# STM32F411CEU6.net
KiCad netlist of a schematic drawn in Altium Designer
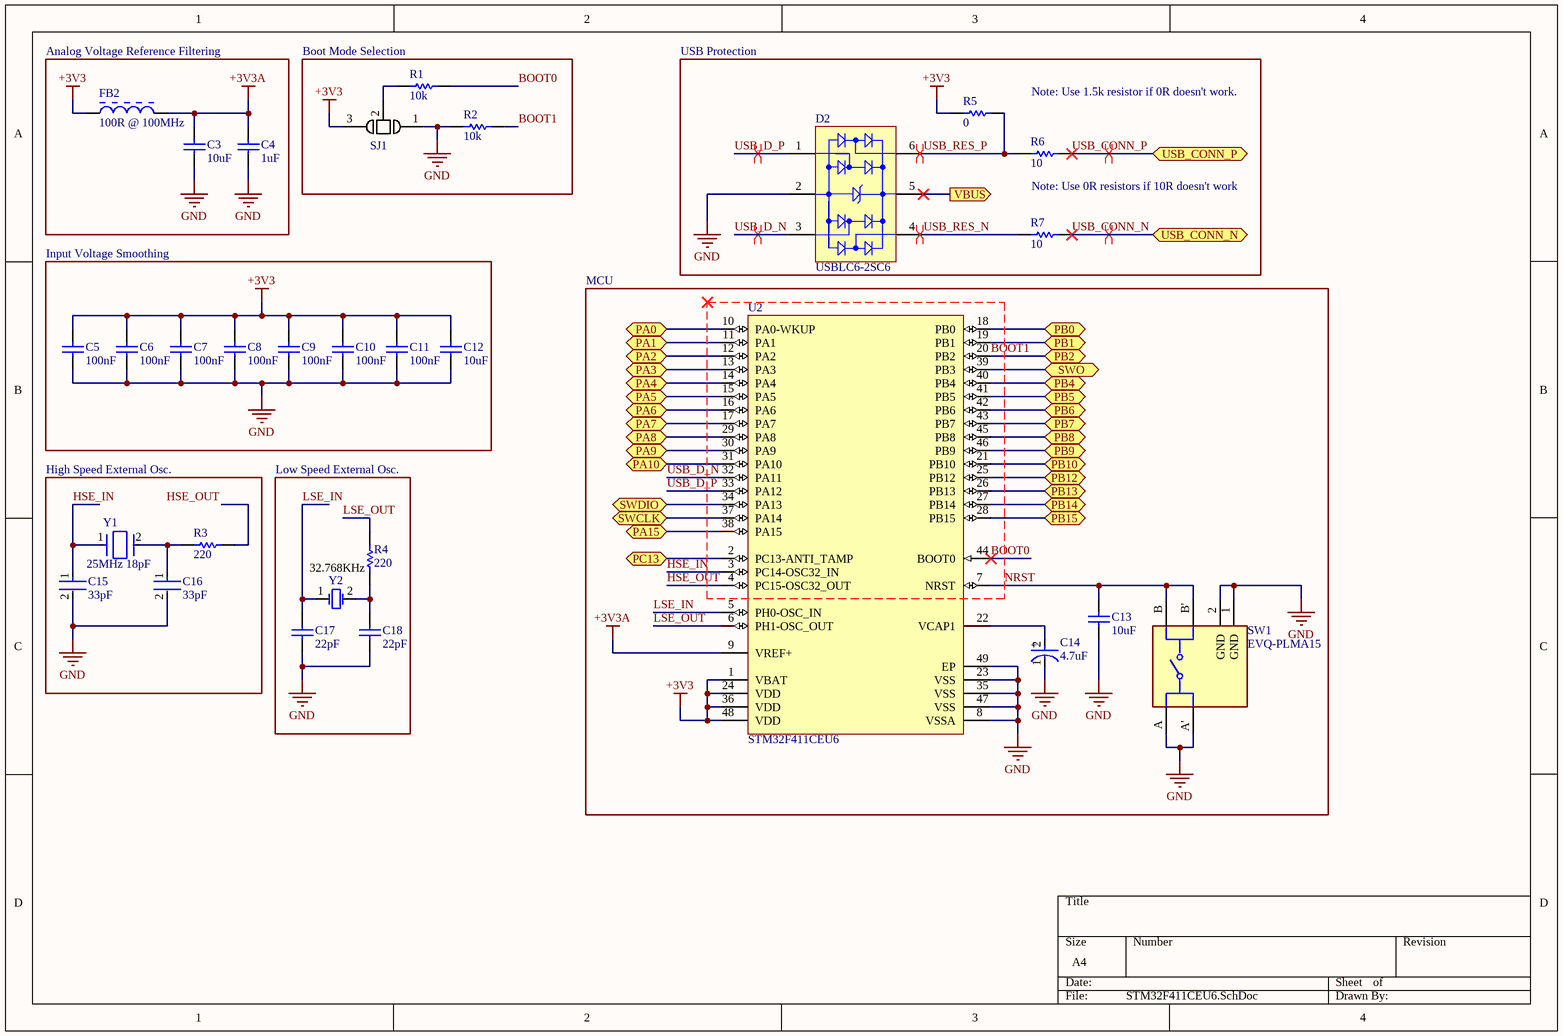
[diagram p0: STM32F411CEU6.SchDoc]

(export (version "E")
  (design (tool "Eeschema 10.0.6"))
  (components
    (comp (ref "C3")
      (value "10uF")
      (footprint "CAPC3216X180X50LL20T30")
      (description "Chip Capacitor, 10 uF, +/- 10%, 25 V, -55 to 85 degC, 1206 (3216 Metric), RoHS, Tape and Reel")
      (fields
        (field (name "MANUFACTURER") "Samsung Electro-Mechanics")
        (field (name "MANUFACTURER PART NUMBER") "CL31A106KAHNNNE")
      )
      (libsource (lib "Altium Content Vault") (part "CAP-NP-2"))
    )
    (comp (ref "C4")
      (value "1uF")
      (footprint "CAPC2013X140X50NL20T25")
      (fields
        (field (name "PART NUMBER") "C0805C105J4RACTU")
        (field (name "MANUFACTURER") "Kemet")
        (field (name "TOLERANCE") "5%")
      )
      (libsource (lib "Altium Content Vault") (part "CAP"))
    )
    (comp (ref "C5")
      (value "100nF")
      (footprint "CAPC2013X94X50LL20T25")
      (description "Chip Capacitor, 0.1 uF, +/- 5%, 50 V, -55 to 125 degC, 0805 (2012 Metric), RoHS, Tape and Reel")
      (fields (field (name "TOLERANCE") "5%") (field (name "MANUFACTURER") "AVX"))
      (libsource (lib "Altium Content Vault") (part "CAP-NP-2"))
    )
    (comp (ref "C6")
      (value "100nF")
      (footprint "CAPC2013X94X50LL20T25")
      (description "Chip Capacitor, 0.1 uF, +/- 5%, 50 V, -55 to 125 degC, 0805 (2012 Metric), RoHS, Tape and Reel")
      (fields (field (name "TOLERANCE") "5%") (field (name "MANUFACTURER") "AVX"))
      (libsource (lib "Altium Content Vault") (part "CAP-NP-2"))
    )
    (comp (ref "C7")
      (value "100nF")
      (footprint "CAPC2013X94X50LL20T25")
      (description "Chip Capacitor, 0.1 uF, +/- 5%, 50 V, -55 to 125 degC, 0805 (2012 Metric), RoHS, Tape and Reel")
      (fields (field (name "TOLERANCE") "5%") (field (name "MANUFACTURER") "AVX"))
      (libsource (lib "Altium Content Vault") (part "CAP-NP-2"))
    )
    (comp (ref "C8")
      (value "100nF")
      (footprint "CAPC2013X94X50LL20T25")
      (description "Chip Capacitor, 0.1 uF, +/- 5%, 50 V, -55 to 125 degC, 0805 (2012 Metric), RoHS, Tape and Reel")
      (fields (field (name "TOLERANCE") "5%") (field (name "MANUFACTURER") "AVX"))
      (libsource (lib "Altium Content Vault") (part "CAP-NP-2"))
    )
    (comp (ref "C9")
      (value "100nF")
      (footprint "CAPC2013X94X50LL20T25")
      (description "Chip Capacitor, 0.1 uF, +/- 5%, 50 V, -55 to 125 degC, 0805 (2012 Metric), RoHS, Tape and Reel")
      (fields (field (name "TOLERANCE") "5%") (field (name "MANUFACTURER") "AVX"))
      (libsource (lib "Altium Content Vault") (part "CAP-NP-2"))
    )
    (comp (ref "C10")
      (value "100nF")
      (footprint "CAPC2013X94X50LL20T25")
      (description "Chip Capacitor, 0.1 uF, +/- 5%, 50 V, -55 to 125 degC, 0805 (2012 Metric), RoHS, Tape and Reel")
      (fields (field (name "TOLERANCE") "5%") (field (name "MANUFACTURER") "AVX"))
      (libsource (lib "Altium Content Vault") (part "CAP-NP-2"))
    )
    (comp (ref "C11")
      (value "100nF")
      (footprint "CAPC2013X94X50LL20T25")
      (description "Chip Capacitor, 0.1 uF, +/- 5%, 50 V, -55 to 125 degC, 0805 (2012 Metric), RoHS, Tape and Reel")
      (fields (field (name "TOLERANCE") "5%") (field (name "MANUFACTURER") "AVX"))
      (libsource (lib "Altium Content Vault") (part "CAP-NP-2"))
    )
    (comp (ref "C12")
      (value "10uF")
      (footprint "CAPC3216X180X50LL20T30")
      (description "Chip Capacitor, 10 uF, +/- 10%, 25 V, -55 to 85 degC, 1206 (3216 Metric), RoHS, Tape and Reel")
      (fields
        (field (name "MANUFACTURER") "Samsung Electro-Mechanics")
        (field (name "MANUFACTURER PART NUMBER") "CL31A106KAHNNNE")
      )
      (libsource (lib "Altium Content Vault") (part "CAP-NP-2"))
    )
    (comp (ref "C13")
      (value "10uF")
      (footprint "CAPC3216X180X50LL20T30")
      (description "Chip Capacitor, 10 uF, +/- 10%, 25 V, -55 to 85 degC, 1206 (3216 Metric), RoHS, Tape and Reel")
      (fields
        (field (name "MANUFACTURER") "Samsung Electro-Mechanics")
        (field (name "MANUFACTURER PART NUMBER") "CL31A106KAHNNNE")
      )
      (libsource (lib "Altium Content Vault") (part "CAP-NP-2"))
    )
    (comp (ref "C14")
      (value "4.7uF")
      (footprint "FP-F38M-MFG")
      (description "CAP TANT POLY 4.7UF 10V SMD")
      (fields
        (field (name "TOLERANCE") "20%")
        (field (name "OCTOPART") "https://octopart.com/f381a475mma-avx-30375031")
      )
      (libsource (lib "Altium Content Vault") (part "cf48714ba7e38822c1575c7ec0b6d1f"))
    )
    (comp (ref "C15")
      (value "33pF")
      (footprint "FP-CL790-IPC_C")
      (description "Cap Ceramic 33pF 50V C0G ±5% SMD 0402 +125°C Paper T/R")
      (fields (field (name "TOLERANCE") "5%") (field (name "VOLTAGE") "50V"))
      (libsource (lib "Altium Content Vault") (part "b4654b650e69147ec39a6b967a45e02"))
    )
    (comp (ref "C16")
      (value "33pF")
      (footprint "FP-CL790-IPC_C")
      (description "Cap Ceramic 33pF 50V C0G ±5% SMD 0402 +125°C Paper T/R")
      (fields (field (name "TOLERANCE") "5%") (field (name "VOLTAGE") "50V"))
      (libsource (lib "Altium Content Vault") (part "b4654b650e69147ec39a6b967a45e02"))
    )
    (comp (ref "C17")
      (value "22pF")
      (footprint "CAPC2012X88X50ML20T25")
      (fields
        (field (name "MANUFACTURER") "Kemet")
        (field (name "PART NUMBER") "C0805C220J5GACTU")
        (field (name "TOLERANCE") "5%")
      )
      (libsource (lib "Altium Content Vault") (part "CAP"))
    )
    (comp (ref "C18")
      (value "22pF")
      (footprint "CAPC2012X88X50ML20T25")
      (fields
        (field (name "MANUFACTURER") "Kemet")
        (field (name "PART NUMBER") "C0805C220J5GACTU")
        (field (name "TOLERANCE") "5%")
      )
      (libsource (lib "Altium Content Vault") (part "CAP"))
    )
    (comp (ref "D2")
      (value "USBLC6-2SC6")
      (footprint "STM-SOT23-6L_V")
      (description "Very low capacitance ESD protection, 3.5 pF, -40 to 125 degC, 6-Pin SOT23, RoHS, Tape and Reel")
      (fields (field (name "MANUFACTURER") "STMicroelectronics"))
      (libsource (lib "Altium Content Vault") (part "STM-USB_DVI_HDMIULC6-4SC6X-SOT23-6L"))
    )
    (comp (ref "FB2")
      (value "100R @ 100MHz")
      (footprint "MURA-BLM18PG_KG-B25-CHIP-2_V1")
      (description "MURATA - BLM18PG121SN1D - FERRITE, BEAD, 0603, 0.05OHM, 2A")
      (fields (field (name "PARTNUMBER") "BLM18PG121SN1D") (field (name "MANUFACTURER") "Murata"))
      (libsource (lib "Altium Content Vault") (part "MURA-FB-2"))
    )
    (comp (ref "R1")
      (value "10k")
      (footprint "RESC2013X70X40LL20T20")
      (fields
        (field (name "PART NUMBER") "ERJ-6GEYJ103V")
        (field (name "MANUFACTURER") "Panasonic")
        (field (name "TOLERANCE") "5%")
      )
      (libsource (lib "Altium Content Vault") (part "RES"))
    )
    (comp (ref "R2")
      (value "10k")
      (footprint "RESC2013X70X40LL20T20")
      (fields
        (field (name "PART NUMBER") "ERJ-6GEYJ103V")
        (field (name "MANUFACTURER") "Panasonic")
        (field (name "TOLERANCE") "5%")
      )
      (libsource (lib "Altium Content Vault") (part "RES"))
    )
    (comp (ref "R3")
      (value "220")
      (footprint "RESC2013X70X40NL20T20")
      (fields
        (field (name "PART NUMBER") "ERJ6ENF2200V")
        (field (name "MANUFACTURER") "Panasonic")
        (field (name "MANUFACTURER PART NUMBER") "ERJ-6ENF2200V")
      )
      (libsource (lib "Altium Content Vault") (part "RES"))
    )
    (comp (ref "R4")
      (value "220")
      (footprint "RESC2013X70X40NL20T20")
      (fields
        (field (name "PART NUMBER") "ERJ6ENF2200V")
        (field (name "MANUFACTURER") "Panasonic")
        (field (name "MANUFACTURER PART NUMBER") "ERJ-6ENF2200V")
      )
      (libsource (lib "Altium Content Vault") (part "RES"))
    )
    (comp (ref "R5")
      (value "0")
      (footprint "RESC2013X70X40NL20T20")
      (description "Chip Resistor, 0 Ohm, +/- 1%, 0.125 W, -55 to 155 degC, 0805 (2012 Metric), RoHS, Tape and Reel")
      (fields (field (name "PARTNUMBER") "ERJ-6GEY0R00V") (field (name "TOLERANCE") "5%"))
      (libsource (lib "Altium Content Vault") (part "RES-2"))
    )
    (comp (ref "R6")
      (value "10")
      (footprint "RESC2013X70X40LL20T20")
      (fields
        (field (name "PART NUMBER") "ERJ-6GEYJ100V")
        (field (name "MANUFACTURER") "Panasonic")
        (field (name "TOLERANCE") "5%")
      )
      (libsource (lib "Altium Content Vault") (part "RES"))
    )
    (comp (ref "R7")
      (value "10")
      (footprint "RESC2013X70X40LL20T20")
      (fields
        (field (name "PART NUMBER") "ERJ-6GEYJ100V")
        (field (name "MANUFACTURER") "Panasonic")
        (field (name "TOLERANCE") "5%")
      )
      (libsource (lib "Altium Content Vault") (part "RES"))
    )
    (comp (ref "SJ1")
      (value "Switchable Jumper")
      (footprint "6mil Switchable")
      (description "Switchable Solder Jumper to choose between two connections.")
      (libsource (lib "Solder Jumpers") (part "Switchable Jumper"))
    )
    (comp (ref "SW1")
      (value "EVQ-PLMA15")
      (footprint "FP-EVQ-PLMA15-MFG")
      (description "SWITCH TACTILE SPST-NO 0.02A 15V")
      (fields
        (field (name "OCTOPART") "https://octopart.com/evq-plma15-panasonic-39850235")
        (field (name "MANUFACTURER") "Panasonic Electronic Components")
      )
      (libsource (lib "Altium Content Vault") (part "fc7b47d2e4813f0909612a6c4f63938"))
    )
    (comp (ref "U2")
      (value "STM32F411CEU6")
      (footprint "STM-UFQFPN48_L")
      (fields (field (name "MANUFACTURER") "STMicroelectronics"))
      (libsource (lib "Altium Content Vault") (part "MC-ARM-STM32F411-UFQFPN48"))
    )
    (comp (ref "Y1")
      (value "25MHz 18pF")
      (footprint "FP-7A-MFG")
      (description "CRYSTAL 25.0000MHZ 18PF SMD")
      (fields (field (name "TOLERANCE") "30ppm") (field (name "MANUFACTURER") "TXC"))
      (libsource (lib "Altium Content Vault") (part "c23a69dc6c9e2f18f2079038eb95dd1"))
    )
    (comp (ref "Y2")
      (value "32.768KHz")
      (footprint "CMHT-CM315D-2_V")
      (description "Turning Fork Crystal Unit, 32.768 KHz, -40 to 85 degC, 2-Pin SMD, RoHS, Tape and Reel")
      (fields
        (field (name "MANUFACTURER") "Citizen Micro HumanTech")
        (field (name "MANUFACTURER PART NUMBER") "CM315D32768DZFT")
      )
      (libsource (lib "Altium Content Vault") (part "XTAL-1-2-2"))
    )
  )
  (nets
    (net (code "1") (name "+3V3") (class "Default")
      (node (ref "C10") (pin "2") (pinfunction "2_2") (pintype "passive"))
      (node (ref "C11") (pin "2") (pinfunction "2_2") (pintype "passive"))
      (node (ref "C12") (pin "2") (pinfunction "2_2") (pintype "passive"))
      (node (ref "C5") (pin "2") (pinfunction "2_2") (pintype "passive"))
      (node (ref "C6") (pin "2") (pinfunction "2_2") (pintype "passive"))
      (node (ref "C7") (pin "2") (pinfunction "2_2") (pintype "passive"))
      (node (ref "C8") (pin "2") (pinfunction "2_2") (pintype "passive"))
      (node (ref "C9") (pin "2") (pinfunction "2_2") (pintype "passive"))
      (node (ref "FB2") (pin "1") (pinfunction "1_1") (pintype "passive"))
      (node (ref "R5") (pin "2") (pinfunction "2_2") (pintype "passive"))
      (node (ref "SJ1") (pin "3") (pintype "passive"))
      (node (ref "U2") (pin "1") (pinfunction "VBAT_1") (pintype "power_in"))
      (node (ref "U2") (pin "24") (pinfunction "VDD_24") (pintype "power_in"))
      (node (ref "U2") (pin "36") (pinfunction "VDD_36") (pintype "power_in"))
      (node (ref "U2") (pin "48") (pinfunction "VDD_48") (pintype "power_in"))
    )
    (net (code "2") (name "+3V3A") (class "Default")
      (node (ref "C3") (pin "2") (pinfunction "2_2") (pintype "passive"))
      (node (ref "C4") (pin "2") (pinfunction "2_2") (pintype "passive"))
      (node (ref "FB2") (pin "2") (pinfunction "2_2") (pintype "passive"))
      (node (ref "U2") (pin "9") (pinfunction "VREF+_9") (pintype "power_in"))
    )
    (net (code "3") (name "/BOOT0") (class "Default")
      (node (ref "R1") (pin "2") (pinfunction "2_2") (pintype "passive"))
      (node (ref "U2") (pin "44") (pinfunction "BOOT0_44") (pintype "input"))
    )
    (net (code "4") (name "/BOOT1") (class "Default")
      (node (ref "R2") (pin "2") (pinfunction "2_2") (pintype "passive"))
      (node (ref "U2") (pin "20") (pinfunction "PB2_20") (pintype "bidirectional"))
    )
    (net (code "5") (name "/HSE_IN") (class "Default")
      (node (ref "C15") (pin "1") (pinfunction "1_1") (pintype "passive"))
      (node (ref "U2") (pin "3") (pinfunction "PC14-OSC32_IN_3") (pintype "bidirectional"))
      (node (ref "Y1") (pin "1") (pinfunction "1_1") (pintype "passive"))
    )
    (net (code "6") (name "/HSE_OUT") (class "Default")
      (node (ref "R3") (pin "2") (pinfunction "2_2") (pintype "passive"))
      (node (ref "U2") (pin "4") (pinfunction "PC15-OSC32_OUT_4") (pintype "bidirectional"))
    )
    (net (code "7") (name "/LSE_IN") (class "Default")
      (node (ref "C17") (pin "2") (pinfunction "2_2") (pintype "passive"))
      (node (ref "U2") (pin "5") (pinfunction "PH0-OSC_IN_5") (pintype "bidirectional"))
      (node (ref "Y2") (pin "1") (pinfunction "1_1") (pintype "passive"))
    )
    (net (code "8") (name "/LSE_OUT") (class "Default")
      (node (ref "R4") (pin "2") (pinfunction "2_2") (pintype "passive"))
      (node (ref "U2") (pin "6") (pinfunction "PH1-OSC_OUT_6") (pintype "bidirectional"))
    )
    (net (code "9") (name "/NRST") (class "Default")
      (node (ref "C13") (pin "2") (pinfunction "2_2") (pintype "passive"))
      (node (ref "SW1") (pin "B") (pinfunction "B_B") (pintype "passive"))
      (node (ref "SW1") (pin "B'") (pinfunction "B'_B'") (pintype "passive"))
      (node (ref "U2") (pin "7") (pinfunction "NRST_7") (pintype "bidirectional"))
    )
    (net (code "10") (name "/PA0") (class "Default")
      (node (ref "U2") (pin "10") (pinfunction "PA0-WKUP_10") (pintype "bidirectional"))
    )
    (net (code "11") (name "/PA1") (class "Default")
      (node (ref "U2") (pin "11") (pinfunction "PA1_11") (pintype "bidirectional"))
    )
    (net (code "12") (name "/PA2") (class "Default")
      (node (ref "U2") (pin "12") (pinfunction "PA2_12") (pintype "bidirectional"))
    )
    (net (code "13") (name "/PA3") (class "Default")
      (node (ref "U2") (pin "13") (pinfunction "PA3_13") (pintype "bidirectional"))
    )
    (net (code "14") (name "/PA4") (class "Default")
      (node (ref "U2") (pin "14") (pinfunction "PA4_14") (pintype "bidirectional"))
    )
    (net (code "15") (name "/PA5") (class "Default")
      (node (ref "U2") (pin "15") (pinfunction "PA5_15") (pintype "bidirectional"))
    )
    (net (code "16") (name "/PA6") (class "Default")
      (node (ref "U2") (pin "16") (pinfunction "PA6_16") (pintype "bidirectional"))
    )
    (net (code "17") (name "/PA7") (class "Default")
      (node (ref "U2") (pin "17") (pinfunction "PA7_17") (pintype "bidirectional"))
    )
    (net (code "18") (name "/PA8") (class "Default")
      (node (ref "U2") (pin "29") (pinfunction "PA8_29") (pintype "bidirectional"))
    )
    (net (code "19") (name "/PA9") (class "Default")
      (node (ref "U2") (pin "30") (pinfunction "PA9_30") (pintype "bidirectional"))
    )
    (net (code "20") (name "/PA10") (class "Default")
      (node (ref "U2") (pin "31") (pinfunction "PA10_31") (pintype "bidirectional"))
    )
    (net (code "21") (name "/PA15") (class "Default")
      (node (ref "U2") (pin "38") (pinfunction "PA15_38") (pintype "bidirectional"))
    )
    (net (code "22") (name "/PB0") (class "Default")
      (node (ref "U2") (pin "18") (pinfunction "PB0_18") (pintype "bidirectional"))
    )
    (net (code "23") (name "/PB1") (class "Default")
      (node (ref "U2") (pin "19") (pinfunction "PB1_19") (pintype "bidirectional"))
    )
    (net (code "24") (name "/PB4") (class "Default")
      (node (ref "U2") (pin "40") (pinfunction "PB4_40") (pintype "bidirectional"))
    )
    (net (code "25") (name "/PB5") (class "Default")
      (node (ref "U2") (pin "41") (pinfunction "PB5_41") (pintype "bidirectional"))
    )
    (net (code "26") (name "/PB6") (class "Default")
      (node (ref "U2") (pin "42") (pinfunction "PB6_42") (pintype "bidirectional"))
    )
    (net (code "27") (name "/PB7") (class "Default")
      (node (ref "U2") (pin "43") (pinfunction "PB7_43") (pintype "bidirectional"))
    )
    (net (code "28") (name "/PB8") (class "Default")
      (node (ref "U2") (pin "45") (pinfunction "PB8_45") (pintype "bidirectional"))
    )
    (net (code "29") (name "/PB9") (class "Default")
      (node (ref "U2") (pin "46") (pinfunction "PB9_46") (pintype "bidirectional"))
    )
    (net (code "30") (name "/PB10") (class "Default")
      (node (ref "U2") (pin "21") (pinfunction "PB10_21") (pintype "bidirectional"))
    )
    (net (code "31") (name "/PB12") (class "Default")
      (node (ref "U2") (pin "25") (pinfunction "PB12_25") (pintype "bidirectional"))
    )
    (net (code "32") (name "/PB13") (class "Default")
      (node (ref "U2") (pin "26") (pinfunction "PB13_26") (pintype "bidirectional"))
    )
    (net (code "33") (name "/PB14") (class "Default")
      (node (ref "U2") (pin "27") (pinfunction "PB14_27") (pintype "bidirectional"))
    )
    (net (code "34") (name "/PB15") (class "Default")
      (node (ref "U2") (pin "28") (pinfunction "PB15_28") (pintype "bidirectional"))
    )
    (net (code "35") (name "/PC13") (class "Default")
      (node (ref "U2") (pin "2") (pinfunction "PC13-ANTI_TAMP_2") (pintype "bidirectional"))
    )
    (net (code "36") (name "/SWCLK") (class "Default")
      (node (ref "U2") (pin "37") (pinfunction "PA14_37") (pintype "bidirectional"))
    )
    (net (code "37") (name "/SWDIO") (class "Default")
      (node (ref "U2") (pin "34") (pinfunction "PA13_34") (pintype "bidirectional"))
    )
    (net (code "38") (name "/SWO") (class "Default")
      (node (ref "U2") (pin "39") (pinfunction "PB3_39") (pintype "bidirectional"))
    )
    (net (code "39") (name "/USB_CONN_N") (class "Default")
      (node (ref "R7") (pin "2") (pinfunction "2_2") (pintype "passive+no_connect"))
    )
    (net (code "40") (name "/USB_CONN_P") (class "Default")
      (node (ref "R6") (pin "2") (pinfunction "2_2") (pintype "passive+no_connect"))
    )
    (net (code "41") (name "/USB_D_N") (class "Default")
      (node (ref "D2") (pin "3") (pinfunction "I/O_2_3") (pintype "passive"))
      (node (ref "U2") (pin "32") (pinfunction "PA11_32") (pintype "bidirectional"))
    )
    (net (code "42") (name "/USB_D_P") (class "Default")
      (node (ref "D2") (pin "1") (pinfunction "I/O_1_1") (pintype "passive"))
      (node (ref "U2") (pin "33") (pinfunction "PA12_33") (pintype "bidirectional"))
    )
    (net (code "43") (name "/USB_RES_N") (class "Default")
      (node (ref "D2") (pin "4") (pinfunction "I/O_3_4") (pintype "passive"))
      (node (ref "R7") (pin "1") (pinfunction "1_1") (pintype "passive"))
    )
    (net (code "44") (name "/USB_RES_P") (class "Default")
      (node (ref "D2") (pin "6") (pinfunction "I/O_4_6") (pintype "passive"))
      (node (ref "R5") (pin "1") (pinfunction "1_1") (pintype "passive"))
      (node (ref "R6") (pin "1") (pinfunction "1_1") (pintype "passive"))
    )
    (net (code "45") (name "/VBUS") (class "Default")
      (node (ref "D2") (pin "5") (pinfunction "VBUS_5") (pintype "passive+no_connect"))
    )
    (net (code "46") (name "GND") (class "Default")
      (node (ref "C10") (pin "1") (pinfunction "1_1") (pintype "passive"))
      (node (ref "C11") (pin "1") (pinfunction "1_1") (pintype "passive"))
      (node (ref "C12") (pin "1") (pinfunction "1_1") (pintype "passive"))
      (node (ref "C13") (pin "1") (pinfunction "1_1") (pintype "passive"))
      (node (ref "C14") (pin "1") (pinfunction "C_1") (pintype "passive"))
      (node (ref "C15") (pin "2") (pinfunction "2_2") (pintype "passive"))
      (node (ref "C16") (pin "2") (pinfunction "2_2") (pintype "passive"))
      (node (ref "C17") (pin "1") (pinfunction "1_1") (pintype "passive"))
      (node (ref "C18") (pin "1") (pinfunction "1_1") (pintype "passive"))
      (node (ref "C3") (pin "1") (pinfunction "1_1") (pintype "passive"))
      (node (ref "C4") (pin "1") (pinfunction "1_1") (pintype "passive"))
      (node (ref "C5") (pin "1") (pinfunction "1_1") (pintype "passive"))
      (node (ref "C6") (pin "1") (pinfunction "1_1") (pintype "passive"))
      (node (ref "C7") (pin "1") (pinfunction "1_1") (pintype "passive"))
      (node (ref "C8") (pin "1") (pinfunction "1_1") (pintype "passive"))
      (node (ref "C9") (pin "1") (pinfunction "1_1") (pintype "passive"))
      (node (ref "D2") (pin "2") (pinfunction "GND_2") (pintype "passive"))
      (node (ref "R2") (pin "1") (pinfunction "1_1") (pintype "passive"))
      (node (ref "SJ1") (pin "1") (pintype "passive"))
      (node (ref "SW1") (pin "1") (pinfunction "GND_1") (pintype "power_in"))
      (node (ref "SW1") (pin "2") (pinfunction "GND_2") (pintype "power_in"))
      (node (ref "SW1") (pin "A") (pinfunction "A_A") (pintype "passive"))
      (node (ref "SW1") (pin "A'") (pinfunction "A'_A'") (pintype "passive"))
      (node (ref "U2") (pin "23") (pinfunction "VSS_23") (pintype "power_in"))
      (node (ref "U2") (pin "35") (pinfunction "VSS_35") (pintype "power_in"))
      (node (ref "U2") (pin "47") (pinfunction "VSS_47") (pintype "power_in"))
      (node (ref "U2") (pin "49") (pinfunction "EP_49") (pintype "power_in"))
      (node (ref "U2") (pin "8") (pinfunction "VSSA_8") (pintype "power_in"))
    )
    (net (code "47") (name "Net-(C14-A)") (class "Default")
      (node (ref "C14") (pin "2") (pinfunction "A_2") (pintype "passive"))
      (node (ref "U2") (pin "22") (pinfunction "VCAP1_22") (pintype "passive"))
    )
    (net (code "48") (name "Net-(C16-Pad1)") (class "Default")
      (node (ref "C16") (pin "1") (pinfunction "1_1") (pintype "passive"))
      (node (ref "R3") (pin "1") (pinfunction "1_1") (pintype "passive"))
      (node (ref "Y1") (pin "2") (pinfunction "2_2") (pintype "passive"))
    )
    (net (code "49") (name "Net-(C18-Pad2)") (class "Default")
      (node (ref "C18") (pin "2") (pinfunction "2_2") (pintype "passive"))
      (node (ref "R4") (pin "1") (pinfunction "1_1") (pintype "passive"))
      (node (ref "Y2") (pin "2") (pinfunction "2_2") (pintype "passive"))
    )
    (net (code "50") (name "Net-(R1-Pad1)") (class "Default")
      (node (ref "R1") (pin "1") (pinfunction "1_1") (pintype "passive"))
      (node (ref "SJ1") (pin "2") (pintype "passive"))
    )
  )
)
